# DM1097_LEFT_OV9282.net
KiCad netlist of a schematic drawn in Altium Designer
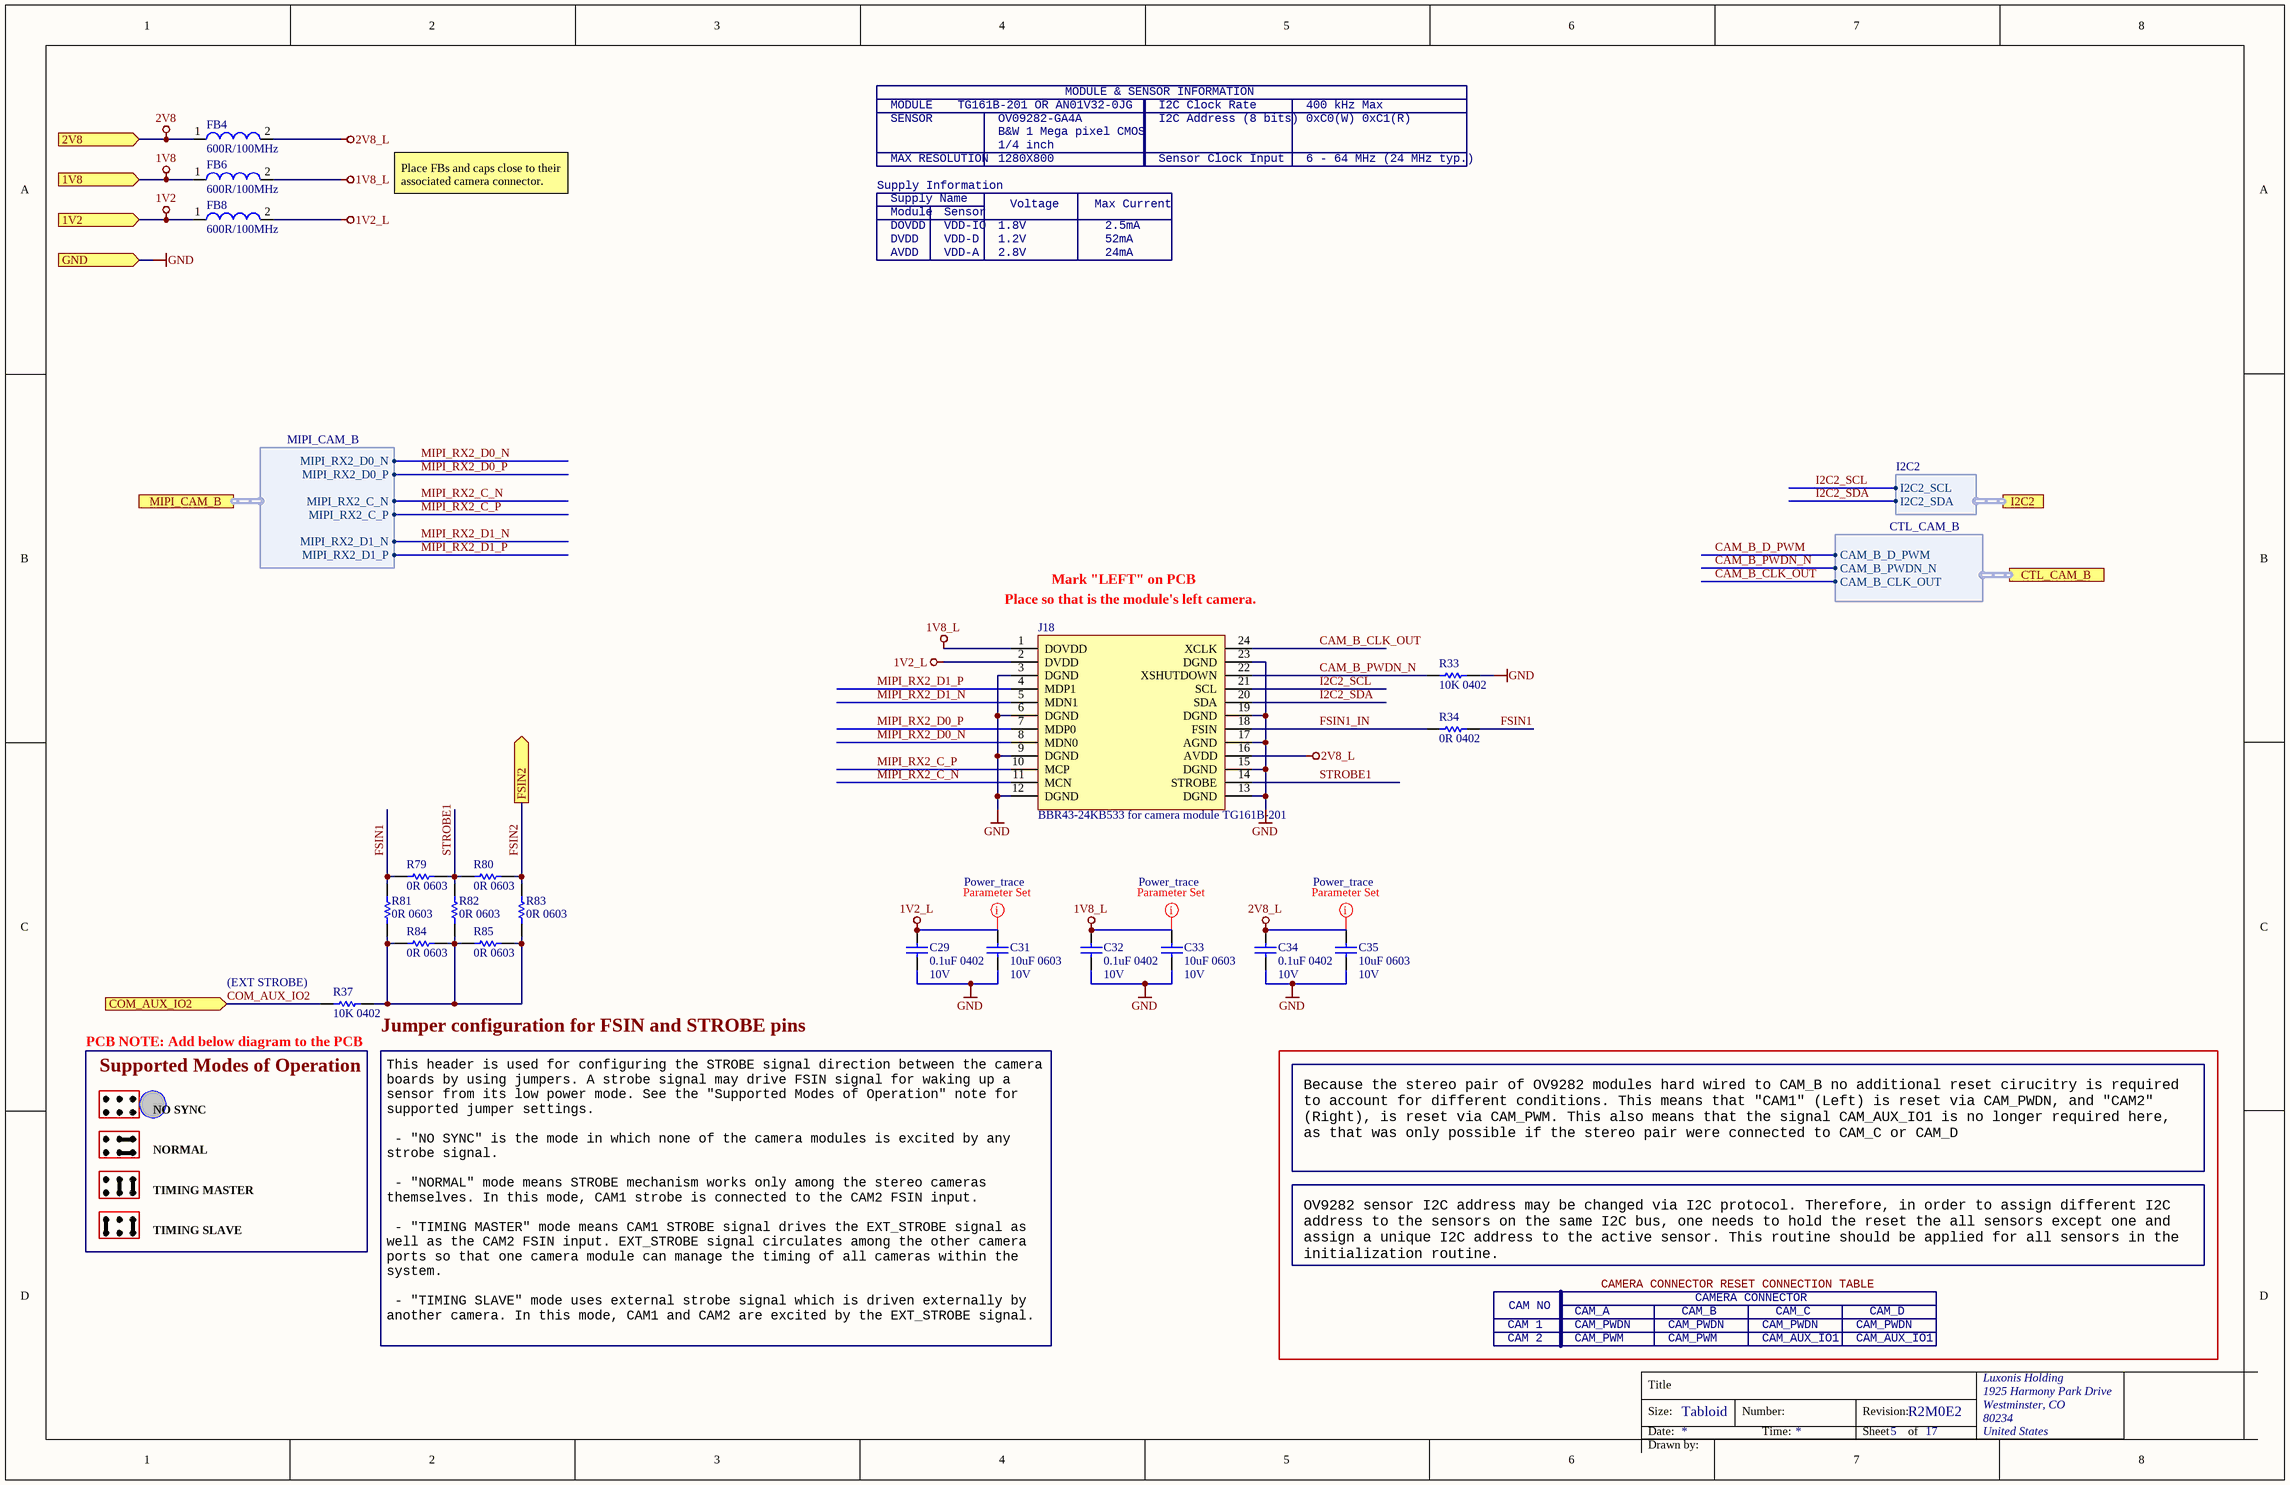
[diagram p0: DM1097_LEFT_OV9282.SchDoc]

(export (version "E")
  (design (tool "Eeschema 10.0.6"))
  (components
    (comp (ref "C29")
      (value "0.1uF 0402")
      (footprint "CAP_Altium_Vault_Generic:CAPC0402(1005)70_N")
      (description "CAP CER 0.1UF 10V X7R 0402 5%")
      (fields (field (name "TOLERANCE") "5%") (field (name "VOLTAGE RATING") "10V"))
      (libsource (lib "LuxonisMaster") (part "GRM155R71A104JA01D"))
    )
    (comp (ref "C31")
      (value "10uF 0603")
      (footprint "CAP_Altium_Vault_Generic:CAPC0603(1608)100_N")
      (description "CAP CER 10UF 10V X5R 0603 20%")
      (fields (field (name "TOLERANCE") "20%") (field (name "VOLTAGE RATING") "10V"))
      (libsource (lib "LuxonisMaster") (part "GRM188R61A106ME69D"))
    )
    (comp (ref "C32")
      (value "0.1uF 0402")
      (footprint "CAP_Altium_Vault_Generic:CAPC0402(1005)70_N")
      (description "CAP CER 0.1UF 10V X7R 0402 5%")
      (fields (field (name "TOLERANCE") "5%") (field (name "VOLTAGE RATING") "10V"))
      (libsource (lib "LuxonisMaster") (part "GRM155R71A104JA01D"))
    )
    (comp (ref "C33")
      (value "10uF 0603")
      (footprint "CAP_Altium_Vault_Generic:CAPC0603(1608)100_N")
      (description "CAP CER 10UF 10V X5R 0603 20%")
      (fields (field (name "TOLERANCE") "20%") (field (name "VOLTAGE RATING") "10V"))
      (libsource (lib "LuxonisMaster") (part "GRM188R61A106ME69D"))
    )
    (comp (ref "C34")
      (value "0.1uF 0402")
      (footprint "CAP_Altium_Vault_Generic:CAPC0402(1005)70_N")
      (description "CAP CER 0.1UF 10V X7R 0402 5%")
      (fields (field (name "TOLERANCE") "5%") (field (name "VOLTAGE RATING") "10V"))
      (libsource (lib "LuxonisMaster") (part "GRM155R71A104JA01D"))
    )
    (comp (ref "C35")
      (value "10uF 0603")
      (footprint "CAP_Altium_Vault_Generic:CAPC0603(1608)100_N")
      (description "CAP CER 10UF 10V X5R 0603 20%")
      (fields (field (name "TOLERANCE") "20%") (field (name "VOLTAGE RATING") "10V"))
      (libsource (lib "LuxonisMaster") (part "GRM188R61A106ME69D"))
    )
    (comp (ref "FB4")
      (value "600R/100MHz")
      (footprint "LuxonisMaster:2508056017Y2")
      (description "FERRITE BEAD, 0.1OHM, 2A, 0805, 600R/100MHz")
      (fields (field (name "TOLERANCE") "25%"))
      (libsource (lib "LuxonisMaster") (part "2508056017Y2"))
    )
    (comp (ref "FB6")
      (value "600R/100MHz")
      (footprint "LuxonisMaster:2508056017Y2")
      (description "FERRITE BEAD, 0.1OHM, 2A, 0805, 600R/100MHz")
      (fields (field (name "TOLERANCE") "25%"))
      (libsource (lib "LuxonisMaster") (part "2508056017Y2"))
    )
    (comp (ref "FB8")
      (value "600R/100MHz")
      (footprint "LuxonisMaster:2508056017Y2")
      (description "FERRITE BEAD, 0.1OHM, 2A, 0805, 600R/100MHz")
      (fields (field (name "TOLERANCE") "25%"))
      (libsource (lib "LuxonisMaster") (part "2508056017Y2"))
    )
    (comp (ref "J18")
      (value "BBR43-24KB533 for camera module TG161B-201")
      (footprint "LuxonisMaster:TG161B-201_HD")
      (description "CONN 24 way, 2 row board to board connector SMD")
      (fields (field (name "MANUFACTURER") "ACON"))
      (libsource (lib "LuxonisMaster") (part "TG161B-201_Connector"))
    )
    (comp (ref "R33")
      (value "10K 0402")
      (footprint "RES_Altium_Vault_Generic:RESC0402(1005)_N")
      (fields (field (name "TOLERANCE") "1%"))
      (libsource (lib "LuxonisMaster") (part "RC0402FR-1310KL"))
    )
    (comp (ref "R34")
      (value "0R 0402")
      (footprint "RES_Altium_Vault_Generic:RESC0402(1005)_N")
      (description "RES SMD 0 OHM JUMPER 1/16W 0402")
      (fields (field (name "TOLERANCE") "5%"))
      (libsource (lib "LuxonisMaster") (part "CRCW04020000Z0ED"))
    )
    (comp (ref "R37")
      (value "10K 0402")
      (footprint "RES_Altium_Vault_Generic:RESC0402(1005)_N")
      (fields (field (name "TOLERANCE") "1%"))
      (libsource (lib "LuxonisMaster") (part "RC0402FR-1310KL"))
    )
    (comp (ref "R79")
      (value "0R 0603")
      (footprint "RES_Altium_Vault_Generic:RESC0603(1608)_N")
      (fields (field (name "TOLERANCE") "5%"))
      (libsource (lib "LuxonisMaster") (part "CRCW06030000Z0EA"))
    )
    (comp (ref "R80")
      (value "0R 0603")
      (footprint "RES_Altium_Vault_Generic:RESC0603(1608)_N")
      (fields (field (name "TOLERANCE") "5%"))
      (libsource (lib "LuxonisMaster") (part "CRCW06030000Z0EA"))
    )
    (comp (ref "R81")
      (value "0R 0603")
      (footprint "RES_Altium_Vault_Generic:RESC0603(1608)_N")
      (fields (field (name "TOLERANCE") "5%"))
      (libsource (lib "LuxonisMaster") (part "CRCW06030000Z0EA"))
    )
    (comp (ref "R82")
      (value "0R 0603")
      (footprint "RES_Altium_Vault_Generic:RESC0603(1608)_N")
      (fields (field (name "TOLERANCE") "5%"))
      (libsource (lib "LuxonisMaster") (part "CRCW06030000Z0EA"))
    )
    (comp (ref "R83")
      (value "0R 0603")
      (footprint "RES_Altium_Vault_Generic:RESC0603(1608)_N")
      (fields (field (name "TOLERANCE") "5%"))
      (libsource (lib "LuxonisMaster") (part "CRCW06030000Z0EA"))
    )
    (comp (ref "R84")
      (value "0R 0603")
      (footprint "RES_Altium_Vault_Generic:RESC0603(1608)_N")
      (fields (field (name "TOLERANCE") "5%"))
      (libsource (lib "LuxonisMaster") (part "CRCW06030000Z0EA"))
    )
    (comp (ref "R85")
      (value "0R 0603")
      (footprint "RES_Altium_Vault_Generic:RESC0603(1608)_N")
      (fields (field (name "TOLERANCE") "5%"))
      (libsource (lib "LuxonisMaster") (part "CRCW06030000Z0EA"))
    )
  )
  (nets
    (net (code "4") (name "/CAM_B_CLK_OUT") (class "Default")
      (node (ref "J18") (pin "24") (pinfunction "XCLK_24") (pintype "passive"))
    )
    (net (code "6") (name "/CAM_B_PWDN_N") (class "Default")
      (node (ref "J18") (pin "22") (pinfunction "XSHUTDOWN_22") (pintype "passive"))
      (node (ref "R33") (pin "1") (pinfunction "1_1") (pintype "passive"))
    )
    (net (code "7") (name "/COM_AUX_IO2") (class "Default")
      (node (ref "R37") (pin "1") (pinfunction "1_1") (pintype "passive"))
    )
    (net (code "8") (name "/FSIN1") (class "Default")
      (node (ref "R34") (pin "2") (pinfunction "2_2") (pintype "passive"))
      (node (ref "R79") (pin "1") (pinfunction "1_1") (pintype "passive"))
      (node (ref "R81") (pin "2") (pinfunction "2_2") (pintype "passive"))
    )
    (net (code "9") (name "/FSIN1_IN") (class "Default")
      (node (ref "J18") (pin "18") (pinfunction "FSIN_18") (pintype "passive"))
      (node (ref "R34") (pin "1") (pinfunction "1_1") (pintype "passive"))
    )
    (net (code "10") (name "/FSIN2") (class "Default")
      (node (ref "R80") (pin "2") (pinfunction "2_2") (pintype "passive"))
      (node (ref "R83") (pin "2") (pinfunction "2_2") (pintype "passive"))
    )
    (net (code "11") (name "/I2C2_SCL") (class "Default")
      (node (ref "J18") (pin "21") (pinfunction "SCL_21") (pintype "passive"))
    )
    (net (code "12") (name "/I2C2_SDA") (class "Default")
      (node (ref "J18") (pin "20") (pinfunction "SDA_20") (pintype "passive"))
    )
    (net (code "13") (name "/MIPI_RX2_C_N") (class "Default")
      (node (ref "J18") (pin "11") (pinfunction "MCN_11") (pintype "passive"))
    )
    (net (code "14") (name "/MIPI_RX2_C_P") (class "Default")
      (node (ref "J18") (pin "10") (pinfunction "MCP_10") (pintype "passive"))
    )
    (net (code "15") (name "/MIPI_RX2_D0_N") (class "Default")
      (node (ref "J18") (pin "8") (pinfunction "MDN0_8") (pintype "passive"))
    )
    (net (code "16") (name "/MIPI_RX2_D0_P") (class "Default")
      (node (ref "J18") (pin "7") (pinfunction "MDP0_7") (pintype "passive"))
    )
    (net (code "17") (name "/MIPI_RX2_D1_N") (class "Default")
      (node (ref "J18") (pin "5") (pinfunction "MDN1_5") (pintype "passive"))
    )
    (net (code "18") (name "/MIPI_RX2_D1_P") (class "Default")
      (node (ref "J18") (pin "4") (pinfunction "MDP1_4") (pintype "passive"))
    )
    (net (code "19") (name "/STROBE1") (class "Default")
      (node (ref "J18") (pin "14") (pinfunction "STROBE_14") (pintype "passive"))
      (node (ref "R79") (pin "2") (pinfunction "2_2") (pintype "passive"))
      (node (ref "R80") (pin "1") (pinfunction "1_1") (pintype "passive"))
      (node (ref "R82") (pin "2") (pinfunction "2_2") (pintype "passive"))
    )
    (net (code "23") (name "1V2") (class "Default")
      (node (ref "FB8") (pin "1") (pinfunction "1_1") (pintype "passive"))
    )
    (net (code "24") (name "1V2_L") (class "Default")
      (node (ref "C29") (pin "2") (pinfunction "2_2") (pintype "passive"))
      (node (ref "C31") (pin "2") (pinfunction "2_2") (pintype "passive"))
      (node (ref "FB8") (pin "2") (pinfunction "2_2") (pintype "passive"))
      (node (ref "J18") (pin "2") (pinfunction "DVDD_2") (pintype "passive"))
    )
    (net (code "25") (name "1V8") (class "Default")
      (node (ref "FB6") (pin "1") (pinfunction "1_1") (pintype "passive"))
    )
    (net (code "26") (name "1V8_L") (class "Default")
      (node (ref "C32") (pin "2") (pinfunction "2_2") (pintype "passive"))
      (node (ref "C33") (pin "2") (pinfunction "2_2") (pintype "passive"))
      (node (ref "FB6") (pin "2") (pinfunction "2_2") (pintype "passive"))
      (node (ref "J18") (pin "1") (pinfunction "DOVDD_1") (pintype "passive"))
    )
    (net (code "27") (name "2V8") (class "Default")
      (node (ref "FB4") (pin "1") (pinfunction "1_1") (pintype "passive"))
    )
    (net (code "28") (name "2V8_L") (class "Default")
      (node (ref "C34") (pin "2") (pinfunction "2_2") (pintype "passive"))
      (node (ref "C35") (pin "2") (pinfunction "2_2") (pintype "passive"))
      (node (ref "FB4") (pin "2") (pinfunction "2_2") (pintype "passive"))
      (node (ref "J18") (pin "16") (pinfunction "AVDD_16") (pintype "passive"))
    )
    (net (code "29") (name "GND") (class "Default")
      (node (ref "C29") (pin "1") (pinfunction "1_1") (pintype "passive"))
      (node (ref "C31") (pin "1") (pinfunction "1_1") (pintype "passive"))
      (node (ref "C32") (pin "1") (pinfunction "1_1") (pintype "passive"))
      (node (ref "C33") (pin "1") (pinfunction "1_1") (pintype "passive"))
      (node (ref "C34") (pin "1") (pinfunction "1_1") (pintype "passive"))
      (node (ref "C35") (pin "1") (pinfunction "1_1") (pintype "passive"))
      (node (ref "J18") (pin "12") (pinfunction "DGND_12") (pintype "passive"))
      (node (ref "J18") (pin "13") (pinfunction "DGND_13") (pintype "passive"))
      (node (ref "J18") (pin "15") (pinfunction "DGND_15") (pintype "passive"))
      (node (ref "J18") (pin "17") (pinfunction "AGND_17") (pintype "passive"))
      (node (ref "J18") (pin "19") (pinfunction "DGND_19") (pintype "passive"))
      (node (ref "J18") (pin "23") (pinfunction "DGND_23") (pintype "passive"))
      (node (ref "J18") (pin "3") (pinfunction "DGND_3") (pintype "passive"))
      (node (ref "J18") (pin "6") (pinfunction "DGND_6") (pintype "passive"))
      (node (ref "J18") (pin "9") (pinfunction "DGND_9") (pintype "passive"))
      (node (ref "R33") (pin "2") (pinfunction "2_2") (pintype "passive"))
    )
    (net (code "30") (name "Net-(R37-Pad2)") (class "Default")
      (node (ref "R37") (pin "2") (pinfunction "2_2") (pintype "passive"))
      (node (ref "R81") (pin "1") (pinfunction "1_1") (pintype "passive"))
      (node (ref "R82") (pin "1") (pinfunction "1_1") (pintype "passive"))
      (node (ref "R83") (pin "1") (pinfunction "1_1") (pintype "passive"))
      (node (ref "R84") (pin "1") (pinfunction "1_1") (pintype "passive"))
      (node (ref "R84") (pin "2") (pinfunction "2_2") (pintype "passive"))
      (node (ref "R85") (pin "1") (pinfunction "1_1") (pintype "passive"))
      (node (ref "R85") (pin "2") (pinfunction "2_2") (pintype "passive"))
    )
  )
)
